# ProgrammableModule2.net
KiCad netlist of a schematic drawn in EAGLE
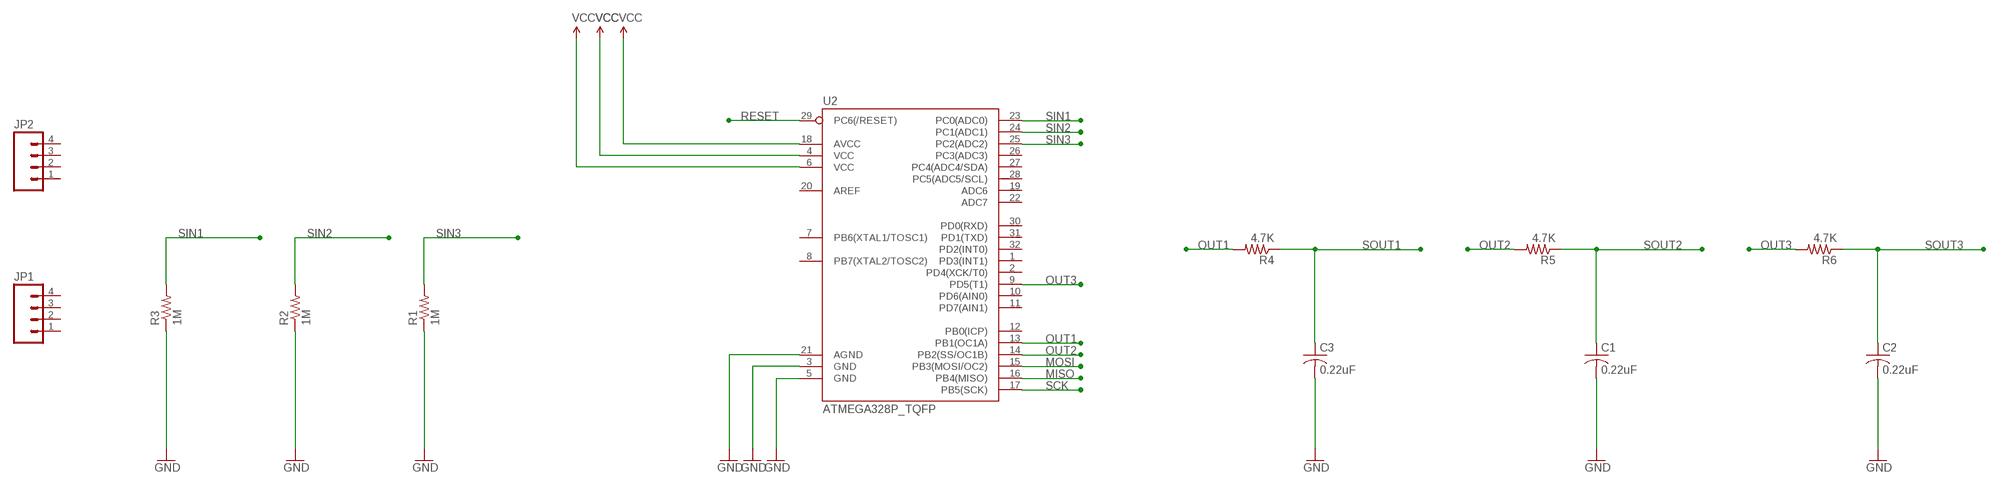
[diagram p0: schematic, sheet 1]

(export (version "E")
  (design (tool "Eeschema 10.0.6"))
  (components
    (comp (ref "C1")
      (value "0.22uF")
      (footprint "eagle-import:C0603")
      (libsource (lib "eagle-import") (part "C-USC0603"))
    )
    (comp (ref "C2")
      (value "0.22uF")
      (footprint "eagle-import:C0603")
      (libsource (lib "eagle-import") (part "C-USC0603"))
    )
    (comp (ref "C3")
      (value "0.22uF")
      (footprint "eagle-import:C0603")
      (libsource (lib "eagle-import") (part "C-USC0603"))
    )
    (comp (ref "JP1")
      (value "M04PTH")
      (footprint "eagle-import:1X04")
      (libsource (lib "eagle-import") (part "M04PTH"))
    )
    (comp (ref "JP2")
      (value "M04PTH")
      (footprint "eagle-import:1X04")
      (libsource (lib "eagle-import") (part "M04PTH"))
    )
    (comp (ref "R1")
      (value "1M")
      (footprint "eagle-import:R0603")
      (libsource (lib "eagle-import") (part "R-US_R0603"))
    )
    (comp (ref "R2")
      (value "1M")
      (footprint "eagle-import:R0603")
      (libsource (lib "eagle-import") (part "R-US_R0603"))
    )
    (comp (ref "R3")
      (value "1M")
      (footprint "eagle-import:R0603")
      (libsource (lib "eagle-import") (part "R-US_R0603"))
    )
    (comp (ref "R4")
      (value "4.7K")
      (footprint "eagle-import:R0603")
      (libsource (lib "eagle-import") (part "R-US_R0603"))
    )
    (comp (ref "R5")
      (value "4.7K")
      (footprint "eagle-import:R0603")
      (libsource (lib "eagle-import") (part "R-US_R0603"))
    )
    (comp (ref "R6")
      (value "4.7K")
      (footprint "eagle-import:R0603")
      (libsource (lib "eagle-import") (part "R-US_R0603"))
    )
    (comp (ref "U2")
      (value "ATMEGA328P_TQFP")
      (footprint "eagle-import:TQFP32-08")
      (libsource (lib "eagle-import") (part "ATMEGA328P_TQFP"))
    )
  )
  (nets
    (net (code "1") (name "/MISO") (class "Default")
      (node (ref "U2") (pin "16") (pinfunction "PB4(MISO)_16") (pintype "bidirectional"))
    )
    (net (code "2") (name "/MOSI") (class "Default")
      (node (ref "U2") (pin "15") (pinfunction "PB3(MOSI/OC2)_15") (pintype "bidirectional"))
    )
    (net (code "3") (name "/OUT1") (class "Default")
      (node (ref "R4") (pin "2") (pinfunction "2_2") (pintype "passive"))
      (node (ref "U2") (pin "13") (pinfunction "PB1(OC1A)_13") (pintype "bidirectional"))
    )
    (net (code "4") (name "/OUT2") (class "Default")
      (node (ref "R5") (pin "2") (pinfunction "2_2") (pintype "passive"))
      (node (ref "U2") (pin "14") (pinfunction "PB2(SS/OC1B)_14") (pintype "bidirectional"))
    )
    (net (code "5") (name "/OUT3") (class "Default")
      (node (ref "R6") (pin "2") (pinfunction "2_2") (pintype "passive"))
      (node (ref "U2") (pin "9") (pinfunction "PD5(T1)_9") (pintype "bidirectional"))
    )
    (net (code "6") (name "/RESET") (class "Default")
      (node (ref "U2") (pin "29") (pinfunction "PC6(/RESET)_29") (pintype "bidirectional"))
    )
    (net (code "7") (name "/SCK") (class "Default")
      (node (ref "U2") (pin "17") (pinfunction "PB5(SCK)_17") (pintype "bidirectional"))
    )
    (net (code "8") (name "/SIN1") (class "Default")
      (node (ref "R3") (pin "2") (pinfunction "2_2") (pintype "passive"))
      (node (ref "U2") (pin "23") (pinfunction "PC0(ADC0)_23") (pintype "bidirectional"))
    )
    (net (code "9") (name "/SIN2") (class "Default")
      (node (ref "R2") (pin "2") (pinfunction "2_2") (pintype "passive"))
      (node (ref "U2") (pin "24") (pinfunction "PC1(ADC1)_24") (pintype "bidirectional"))
    )
    (net (code "10") (name "/SIN3") (class "Default")
      (node (ref "R1") (pin "2") (pinfunction "2_2") (pintype "passive"))
      (node (ref "U2") (pin "25") (pinfunction "PC2(ADC2)_25") (pintype "bidirectional"))
    )
    (net (code "11") (name "/SOUT1") (class "Default")
      (node (ref "C3") (pin "1") (pinfunction "1_1") (pintype "passive"))
      (node (ref "R4") (pin "1") (pinfunction "1_1") (pintype "passive"))
    )
    (net (code "12") (name "/SOUT2") (class "Default")
      (node (ref "C1") (pin "1") (pinfunction "1_1") (pintype "passive"))
      (node (ref "R5") (pin "1") (pinfunction "1_1") (pintype "passive"))
    )
    (net (code "13") (name "/SOUT3") (class "Default")
      (node (ref "C2") (pin "1") (pinfunction "1_1") (pintype "passive"))
      (node (ref "R6") (pin "1") (pinfunction "1_1") (pintype "passive"))
    )
    (net (code "14") (name "GND") (class "Default")
      (node (ref "C1") (pin "2") (pinfunction "2_2") (pintype "passive"))
      (node (ref "C2") (pin "2") (pinfunction "2_2") (pintype "passive"))
      (node (ref "C3") (pin "2") (pinfunction "2_2") (pintype "passive"))
      (node (ref "R1") (pin "1") (pinfunction "1_1") (pintype "passive"))
      (node (ref "R2") (pin "1") (pinfunction "1_1") (pintype "passive"))
      (node (ref "R3") (pin "1") (pinfunction "1_1") (pintype "passive"))
      (node (ref "U2") (pin "21") (pinfunction "AGND_21") (pintype "bidirectional"))
      (node (ref "U2") (pin "3") (pinfunction "GND_3") (pintype "bidirectional"))
      (node (ref "U2") (pin "5") (pinfunction "GND_5") (pintype "bidirectional"))
    )
    (net (code "15") (name "VCC") (class "Default")
      (node (ref "U2") (pin "18") (pinfunction "AVCC_18") (pintype "bidirectional"))
      (node (ref "U2") (pin "4") (pinfunction "VCC_4") (pintype "bidirectional"))
      (node (ref "U2") (pin "6") (pinfunction "VCC_6") (pintype "bidirectional"))
    )
    (net (code "16") (name "unconnected-(JP1-Pad1)") (class "Default")
      (node (ref "JP1") (pin "1") (pinfunction "1_1") (pintype "passive"))
    )
    (net (code "17") (name "unconnected-(JP1-Pad2)") (class "Default")
      (node (ref "JP1") (pin "2") (pinfunction "2_2") (pintype "passive"))
    )
    (net (code "18") (name "unconnected-(JP1-Pad3)") (class "Default")
      (node (ref "JP1") (pin "3") (pinfunction "3_3") (pintype "passive"))
    )
    (net (code "19") (name "unconnected-(JP1-Pad4)") (class "Default")
      (node (ref "JP1") (pin "4") (pinfunction "4_4") (pintype "passive"))
    )
    (net (code "20") (name "unconnected-(JP2-Pad1)") (class "Default")
      (node (ref "JP2") (pin "1") (pinfunction "1_1") (pintype "passive"))
    )
    (net (code "21") (name "unconnected-(JP2-Pad2)") (class "Default")
      (node (ref "JP2") (pin "2") (pinfunction "2_2") (pintype "passive"))
    )
    (net (code "22") (name "unconnected-(JP2-Pad3)") (class "Default")
      (node (ref "JP2") (pin "3") (pinfunction "3_3") (pintype "passive"))
    )
    (net (code "23") (name "unconnected-(JP2-Pad4)") (class "Default")
      (node (ref "JP2") (pin "4") (pinfunction "4_4") (pintype "passive"))
    )
    (net (code "24") (name "unconnected-(U2-ADC6-Pad19)") (class "Default")
      (node (ref "U2") (pin "19") (pinfunction "ADC6_19") (pintype "bidirectional"))
    )
    (net (code "25") (name "unconnected-(U2-ADC7-Pad22)") (class "Default")
      (node (ref "U2") (pin "22") (pinfunction "ADC7_22") (pintype "bidirectional"))
    )
    (net (code "26") (name "unconnected-(U2-AREF-Pad20)") (class "Default")
      (node (ref "U2") (pin "20") (pinfunction "AREF_20") (pintype "bidirectional"))
    )
    (net (code "27") (name "unconnected-(U2-PB0(ICP)-Pad12)") (class "Default")
      (node (ref "U2") (pin "12") (pinfunction "PB0(ICP)_12") (pintype "bidirectional"))
    )
    (net (code "28") (name "unconnected-(U2-PB6(XTAL1{slash}TOSC1)-Pad7)") (class "Default")
      (node (ref "U2") (pin "7") (pinfunction "PB6(XTAL1/TOSC1)_7") (pintype "bidirectional"))
    )
    (net (code "29") (name "unconnected-(U2-PB7(XTAL2{slash}TOSC2)-Pad8)") (class "Default")
      (node (ref "U2") (pin "8") (pinfunction "PB7(XTAL2/TOSC2)_8") (pintype "bidirectional"))
    )
    (net (code "30") (name "unconnected-(U2-PC3(ADC3)-Pad26)") (class "Default")
      (node (ref "U2") (pin "26") (pinfunction "PC3(ADC3)_26") (pintype "bidirectional"))
    )
    (net (code "31") (name "unconnected-(U2-PC4(ADC4{slash}SDA)-Pad27)") (class "Default")
      (node (ref "U2") (pin "27") (pinfunction "PC4(ADC4/SDA)_27") (pintype "bidirectional"))
    )
    (net (code "32") (name "unconnected-(U2-PC5(ADC5{slash}SCL)-Pad28)") (class "Default")
      (node (ref "U2") (pin "28") (pinfunction "PC5(ADC5/SCL)_28") (pintype "bidirectional"))
    )
    (net (code "33") (name "unconnected-(U2-PD0(RXD)-Pad30)") (class "Default")
      (node (ref "U2") (pin "30") (pinfunction "PD0(RXD)_30") (pintype "bidirectional"))
    )
    (net (code "34") (name "unconnected-(U2-PD1(TXD)-Pad31)") (class "Default")
      (node (ref "U2") (pin "31") (pinfunction "PD1(TXD)_31") (pintype "bidirectional"))
    )
    (net (code "35") (name "unconnected-(U2-PD2(INT0)-Pad32)") (class "Default")
      (node (ref "U2") (pin "32") (pinfunction "PD2(INT0)_32") (pintype "bidirectional"))
    )
    (net (code "36") (name "unconnected-(U2-PD3(INT1)-Pad1)") (class "Default")
      (node (ref "U2") (pin "1") (pinfunction "PD3(INT1)_1") (pintype "bidirectional"))
    )
    (net (code "37") (name "unconnected-(U2-PD4(XCK{slash}T0)-Pad2)") (class "Default")
      (node (ref "U2") (pin "2") (pinfunction "PD4(XCK/T0)_2") (pintype "bidirectional"))
    )
    (net (code "38") (name "unconnected-(U2-PD6(AIN0)-Pad10)") (class "Default")
      (node (ref "U2") (pin "10") (pinfunction "PD6(AIN0)_10") (pintype "bidirectional"))
    )
    (net (code "39") (name "unconnected-(U2-PD7(AIN1)-Pad11)") (class "Default")
      (node (ref "U2") (pin "11") (pinfunction "PD7(AIN1)_11") (pintype "bidirectional"))
    )
  )
)
